# Dev_BRD_STM32F030K6T6.net
KiCad netlist of a schematic drawn in Altium Designer
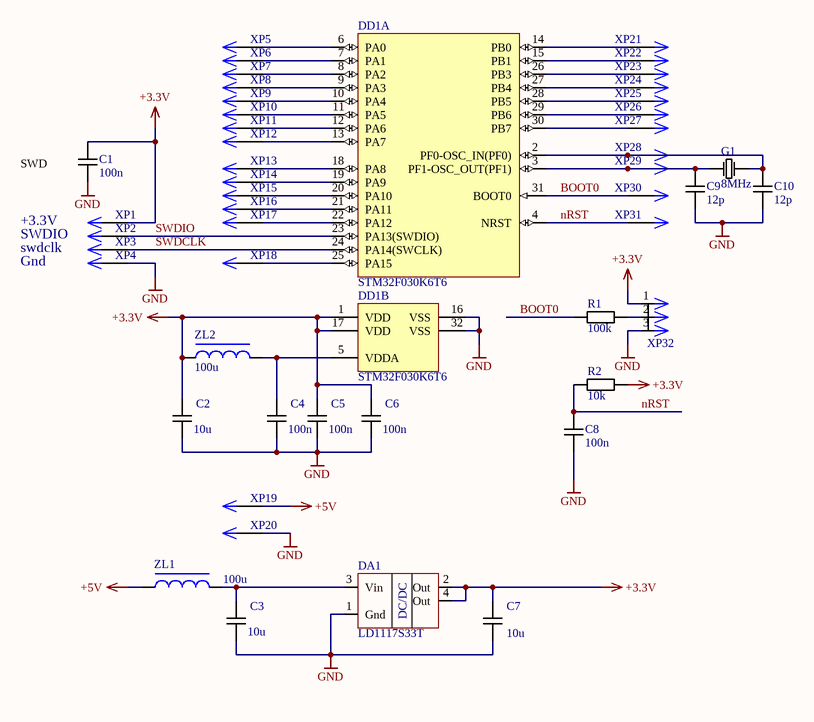
[diagram p0: Dev_BRD_STM32F030K6T6.SchDoc]

(export (version "E")
  (design (tool "Eeschema 10.0.6"))
  (components
    (comp (ref "C1")
      (value "100n")
      (footprint "CAPC1608(0603)N")
      (description "?")
      (fields (field (name "PART NUMBER") "CAPC1608(0603)"))
      (libsource (lib "SssAccesDatbase") (part "Cap"))
    )
    (comp (ref "C2")
      (value "10u")
      (footprint "CAPC1608(0603)N")
      (description "?")
      (fields (field (name "PART NUMBER") "CAPC1608(0603)"))
      (libsource (lib "SssAccesDatbase") (part "Cap"))
    )
    (comp (ref "C3")
      (value "10u")
      (footprint "CAPC1608(0603)N")
      (description "?")
      (fields (field (name "PART NUMBER") "CAPC1608(0603)"))
      (libsource (lib "SssAccesDatbase") (part "Cap"))
    )
    (comp (ref "C4")
      (value "100n")
      (footprint "CAPC1608(0603)N")
      (description "?")
      (fields (field (name "PART NUMBER") "CAPC1608(0603)"))
      (libsource (lib "SssAccesDatbase") (part "Cap"))
    )
    (comp (ref "C5")
      (value "100n")
      (footprint "CAPC1608(0603)N")
      (description "?")
      (fields (field (name "PART NUMBER") "CAPC1608(0603)"))
      (libsource (lib "SssAccesDatbase") (part "Cap"))
    )
    (comp (ref "C6")
      (value "100n")
      (footprint "CAPC1608(0603)N")
      (description "?")
      (fields (field (name "PART NUMBER") "CAPC1608(0603)"))
      (libsource (lib "SssAccesDatbase") (part "Cap"))
    )
    (comp (ref "C7")
      (value "10u")
      (footprint "CAPC1608(0603)N")
      (description "?")
      (fields (field (name "PART NUMBER") "CAPC1608(0603)"))
      (libsource (lib "SssAccesDatbase") (part "Cap"))
    )
    (comp (ref "C8")
      (value "100n")
      (footprint "CAPC1608(0603)N")
      (description "?")
      (fields (field (name "PART NUMBER") "CAPC1608(0603)"))
      (libsource (lib "SssAccesDatbase") (part "Cap"))
    )
    (comp (ref "C9")
      (value "12p")
      (footprint "CAPC1608(0603)N")
      (description "?")
      (fields (field (name "PART NUMBER") "CAPC1608(0603)"))
      (libsource (lib "SssAccesDatbase") (part "Cap"))
    )
    (comp (ref "C10")
      (value "12p")
      (footprint "CAPC1608(0603)N")
      (description "?")
      (fields (field (name "PART NUMBER") "CAPC1608(0603)"))
      (libsource (lib "SssAccesDatbase") (part "Cap"))
    )
    (comp (ref "DA1")
      (value "LD1117S33T")
      (footprint "SOT223_M")
      (description "LDO Voltage Regulators 3.3V 0.8A Positive")
      (fields (field (name "DIGI-KEY PART NUMBER") "?"))
      (libsource (lib "SssAccesDatbase") (part "LD1117S33T"))
    )
    (comp (ref "DD1")
      (value "STM32F030K6T6")
      (footprint "STM-LQFP32_M")
      (description "ARM Microcontrollers - MCU Entry-level ARM Cortex-M0 Value MCU")
      (fields (field (name "MOUSER PART NUMBER") "511-STM32F030K6T6"))
      (libsource (lib "SssAccesDatbase") (part "STM32F030K6T6"))
    )
    (comp (ref "G1")
      (value "8MHz")
      (footprint "HC-49/S")
      (description "Crystal HC-49/S")
      (libsource (lib "SssAccesDatbase") (part "Crystal"))
    )
    (comp (ref "R1")
      (value "100k")
      (footprint "RESC1608(0603)N")
      (fields (field (name "PART NUMBER") "RESC1608(0603)") (field (name "DIGI-KEY PART NUMBER") "???"))
      (libsource (lib "SssAccesDatbase") (part "Resistor general"))
    )
    (comp (ref "R2")
      (value "10k")
      (footprint "RESC1608(0603)N")
      (fields (field (name "PART NUMBER") "RESC1608(0603)") (field (name "DIGI-KEY PART NUMBER") "???"))
      (libsource (lib "") (part "Resistor general_1"))
    )
    (comp (ref "XP1")
      (value "PLS-1")
      (footprint "PLS-1-3D")
      (description "CONN HEADER VERT 1POS")
      (fields
        (field (name "DIGI-KEY PART NUMBER") "S1011EC-01-ND")
        (field (name "MANUFACTURER PART NUMBER") "PRPC001SAAN-RC")
      )
      (libsource (lib "SssAccesDatbase") (part "XP-1_1"))
    )
    (comp (ref "XP2")
      (value "PLS-1")
      (footprint "PLS-1-3D")
      (description "CONN HEADER VERT 1POS")
      (fields
        (field (name "DIGI-KEY PART NUMBER") "S1011EC-01-ND")
        (field (name "MANUFACTURER PART NUMBER") "PRPC001SAAN-RC")
      )
      (libsource (lib "SssAccesDatbase") (part "XP-1_1"))
    )
    (comp (ref "XP3")
      (value "PLS-1")
      (footprint "PLS-1-3D")
      (description "CONN HEADER VERT 1POS")
      (fields
        (field (name "DIGI-KEY PART NUMBER") "S1011EC-01-ND")
        (field (name "MANUFACTURER PART NUMBER") "PRPC001SAAN-RC")
      )
      (libsource (lib "SssAccesDatbase") (part "XP-1_1"))
    )
    (comp (ref "XP4")
      (value "PLS-1")
      (footprint "PLS-1-3D")
      (description "CONN HEADER VERT 1POS")
      (fields
        (field (name "DIGI-KEY PART NUMBER") "S1011EC-01-ND")
        (field (name "MANUFACTURER PART NUMBER") "PRPC001SAAN-RC")
      )
      (libsource (lib "SssAccesDatbase") (part "XP-1_1"))
    )
    (comp (ref "XP5")
      (value "PLS-1")
      (footprint "PLS-1-3D")
      (description "CONN HEADER VERT 1POS")
      (fields
        (field (name "DIGI-KEY PART NUMBER") "S1011EC-01-ND")
        (field (name "MANUFACTURER PART NUMBER") "PRPC001SAAN-RC")
      )
      (libsource (lib "SssAccesDatbase") (part "XP-1_1"))
    )
    (comp (ref "XP6")
      (value "PLS-1")
      (footprint "PLS-1-3D")
      (description "CONN HEADER VERT 1POS")
      (fields
        (field (name "DIGI-KEY PART NUMBER") "S1011EC-01-ND")
        (field (name "MANUFACTURER PART NUMBER") "PRPC001SAAN-RC")
      )
      (libsource (lib "SssAccesDatbase") (part "XP-1_1"))
    )
    (comp (ref "XP7")
      (value "PLS-1")
      (footprint "PLS-1-3D")
      (description "CONN HEADER VERT 1POS")
      (fields
        (field (name "DIGI-KEY PART NUMBER") "S1011EC-01-ND")
        (field (name "MANUFACTURER PART NUMBER") "PRPC001SAAN-RC")
      )
      (libsource (lib "SssAccesDatbase") (part "XP-1_1"))
    )
    (comp (ref "XP8")
      (value "PLS-1")
      (footprint "PLS-1-3D")
      (description "CONN HEADER VERT 1POS")
      (fields
        (field (name "DIGI-KEY PART NUMBER") "S1011EC-01-ND")
        (field (name "MANUFACTURER PART NUMBER") "PRPC001SAAN-RC")
      )
      (libsource (lib "SssAccesDatbase") (part "XP-1_1"))
    )
    (comp (ref "XP9")
      (value "PLS-1")
      (footprint "PLS-1-3D")
      (description "CONN HEADER VERT 1POS")
      (fields
        (field (name "DIGI-KEY PART NUMBER") "S1011EC-01-ND")
        (field (name "MANUFACTURER PART NUMBER") "PRPC001SAAN-RC")
      )
      (libsource (lib "SssAccesDatbase") (part "XP-1_1"))
    )
    (comp (ref "XP10")
      (value "PLS-1")
      (footprint "PLS-1-3D")
      (description "CONN HEADER VERT 1POS")
      (fields
        (field (name "DIGI-KEY PART NUMBER") "S1011EC-01-ND")
        (field (name "MANUFACTURER PART NUMBER") "PRPC001SAAN-RC")
      )
      (libsource (lib "SssAccesDatbase") (part "XP-1_1"))
    )
    (comp (ref "XP11")
      (value "PLS-1")
      (footprint "PLS-1-3D")
      (description "CONN HEADER VERT 1POS")
      (fields
        (field (name "DIGI-KEY PART NUMBER") "S1011EC-01-ND")
        (field (name "MANUFACTURER PART NUMBER") "PRPC001SAAN-RC")
      )
      (libsource (lib "SssAccesDatbase") (part "XP-1_1"))
    )
    (comp (ref "XP12")
      (value "PLS-1")
      (footprint "PLS-1-3D")
      (description "CONN HEADER VERT 1POS")
      (fields
        (field (name "DIGI-KEY PART NUMBER") "S1011EC-01-ND")
        (field (name "MANUFACTURER PART NUMBER") "PRPC001SAAN-RC")
      )
      (libsource (lib "SssAccesDatbase") (part "XP-1_1"))
    )
    (comp (ref "XP13")
      (value "PLS-1")
      (footprint "PLS-1-3D")
      (description "CONN HEADER VERT 1POS")
      (fields
        (field (name "DIGI-KEY PART NUMBER") "S1011EC-01-ND")
        (field (name "MANUFACTURER PART NUMBER") "PRPC001SAAN-RC")
      )
      (libsource (lib "SssAccesDatbase") (part "XP-1_1"))
    )
    (comp (ref "XP14")
      (value "PLS-1")
      (footprint "PLS-1-3D")
      (description "CONN HEADER VERT 1POS")
      (fields
        (field (name "DIGI-KEY PART NUMBER") "S1011EC-01-ND")
        (field (name "MANUFACTURER PART NUMBER") "PRPC001SAAN-RC")
      )
      (libsource (lib "SssAccesDatbase") (part "XP-1_1"))
    )
    (comp (ref "XP15")
      (value "PLS-1")
      (footprint "PLS-1-3D")
      (description "CONN HEADER VERT 1POS")
      (fields
        (field (name "DIGI-KEY PART NUMBER") "S1011EC-01-ND")
        (field (name "MANUFACTURER PART NUMBER") "PRPC001SAAN-RC")
      )
      (libsource (lib "SssAccesDatbase") (part "XP-1_1"))
    )
    (comp (ref "XP16")
      (value "PLS-1")
      (footprint "PLS-1-3D")
      (description "CONN HEADER VERT 1POS")
      (fields
        (field (name "DIGI-KEY PART NUMBER") "S1011EC-01-ND")
        (field (name "MANUFACTURER PART NUMBER") "PRPC001SAAN-RC")
      )
      (libsource (lib "SssAccesDatbase") (part "XP-1_1"))
    )
    (comp (ref "XP17")
      (value "PLS-1")
      (footprint "PLS-1-3D")
      (description "CONN HEADER VERT 1POS")
      (fields
        (field (name "DIGI-KEY PART NUMBER") "S1011EC-01-ND")
        (field (name "MANUFACTURER PART NUMBER") "PRPC001SAAN-RC")
      )
      (libsource (lib "SssAccesDatbase") (part "XP-1_1"))
    )
    (comp (ref "XP18")
      (value "PLS-1")
      (footprint "PLS-1-3D")
      (description "CONN HEADER VERT 1POS")
      (fields
        (field (name "DIGI-KEY PART NUMBER") "S1011EC-01-ND")
        (field (name "MANUFACTURER PART NUMBER") "PRPC001SAAN-RC")
      )
      (libsource (lib "SssAccesDatbase") (part "XP-1_1"))
    )
    (comp (ref "XP19")
      (value "PLS-1")
      (footprint "PLS-1-3D")
      (description "CONN HEADER VERT 1POS")
      (fields
        (field (name "DIGI-KEY PART NUMBER") "S1011EC-01-ND")
        (field (name "MANUFACTURER PART NUMBER") "PRPC001SAAN-RC")
      )
      (libsource (lib "SssAccesDatbase") (part "XP-1_1"))
    )
    (comp (ref "XP20")
      (value "PLS-1")
      (footprint "PLS-1-3D")
      (description "CONN HEADER VERT 1POS")
      (fields
        (field (name "DIGI-KEY PART NUMBER") "S1011EC-01-ND")
        (field (name "MANUFACTURER PART NUMBER") "PRPC001SAAN-RC")
      )
      (libsource (lib "SssAccesDatbase") (part "XP-1_1"))
    )
    (comp (ref "XP21")
      (value "PLS-1")
      (footprint "PLS-1-3D")
      (description "CONN HEADER VERT 1POS")
      (fields
        (field (name "DIGI-KEY PART NUMBER") "S1011EC-01-ND")
        (field (name "MANUFACTURER PART NUMBER") "PRPC001SAAN-RC")
      )
      (libsource (lib "SssAccesDatbase") (part "XP-1_1"))
    )
    (comp (ref "XP22")
      (value "PLS-1")
      (footprint "PLS-1-3D")
      (description "CONN HEADER VERT 1POS")
      (fields
        (field (name "DIGI-KEY PART NUMBER") "S1011EC-01-ND")
        (field (name "MANUFACTURER PART NUMBER") "PRPC001SAAN-RC")
      )
      (libsource (lib "SssAccesDatbase") (part "XP-1_1"))
    )
    (comp (ref "XP23")
      (value "PLS-1")
      (footprint "PLS-1-3D")
      (description "CONN HEADER VERT 1POS")
      (fields
        (field (name "DIGI-KEY PART NUMBER") "S1011EC-01-ND")
        (field (name "MANUFACTURER PART NUMBER") "PRPC001SAAN-RC")
      )
      (libsource (lib "SssAccesDatbase") (part "XP-1_1"))
    )
    (comp (ref "XP24")
      (value "PLS-1")
      (footprint "PLS-1-3D")
      (description "CONN HEADER VERT 1POS")
      (fields
        (field (name "DIGI-KEY PART NUMBER") "S1011EC-01-ND")
        (field (name "MANUFACTURER PART NUMBER") "PRPC001SAAN-RC")
      )
      (libsource (lib "SssAccesDatbase") (part "XP-1_1"))
    )
    (comp (ref "XP25")
      (value "PLS-1")
      (footprint "PLS-1-3D")
      (description "CONN HEADER VERT 1POS")
      (fields
        (field (name "DIGI-KEY PART NUMBER") "S1011EC-01-ND")
        (field (name "MANUFACTURER PART NUMBER") "PRPC001SAAN-RC")
      )
      (libsource (lib "SssAccesDatbase") (part "XP-1_1"))
    )
    (comp (ref "XP26")
      (value "PLS-1")
      (footprint "PLS-1-3D")
      (description "CONN HEADER VERT 1POS")
      (fields
        (field (name "DIGI-KEY PART NUMBER") "S1011EC-01-ND")
        (field (name "MANUFACTURER PART NUMBER") "PRPC001SAAN-RC")
      )
      (libsource (lib "SssAccesDatbase") (part "XP-1_1"))
    )
    (comp (ref "XP27")
      (value "PLS-1")
      (footprint "PLS-1-3D")
      (description "CONN HEADER VERT 1POS")
      (fields
        (field (name "DIGI-KEY PART NUMBER") "S1011EC-01-ND")
        (field (name "MANUFACTURER PART NUMBER") "PRPC001SAAN-RC")
      )
      (libsource (lib "SssAccesDatbase") (part "XP-1_1"))
    )
    (comp (ref "XP28")
      (value "PLS-1")
      (footprint "PLS-1-3D")
      (description "CONN HEADER VERT 1POS")
      (fields
        (field (name "DIGI-KEY PART NUMBER") "S1011EC-01-ND")
        (field (name "MANUFACTURER PART NUMBER") "PRPC001SAAN-RC")
      )
      (libsource (lib "SssAccesDatbase") (part "XP-1_1"))
    )
    (comp (ref "XP29")
      (value "PLS-1")
      (footprint "PLS-1-3D")
      (description "CONN HEADER VERT 1POS")
      (fields
        (field (name "DIGI-KEY PART NUMBER") "S1011EC-01-ND")
        (field (name "MANUFACTURER PART NUMBER") "PRPC001SAAN-RC")
      )
      (libsource (lib "SssAccesDatbase") (part "XP-1_1"))
    )
    (comp (ref "XP30")
      (value "PLS-1")
      (footprint "PLS-1-3D")
      (description "CONN HEADER VERT 1POS")
      (fields
        (field (name "DIGI-KEY PART NUMBER") "S1011EC-01-ND")
        (field (name "MANUFACTURER PART NUMBER") "PRPC001SAAN-RC")
      )
      (libsource (lib "SssAccesDatbase") (part "XP-1_1"))
    )
    (comp (ref "XP31")
      (value "PLS-1")
      (footprint "PLS-1-3D")
      (description "CONN HEADER VERT 1POS")
      (fields
        (field (name "DIGI-KEY PART NUMBER") "S1011EC-01-ND")
        (field (name "MANUFACTURER PART NUMBER") "PRPC001SAAN-RC")
      )
      (libsource (lib "SssAccesDatbase") (part "XP-1_1"))
    )
    (comp (ref "XP32")
      (value "PLS-3")
      (footprint "PLS-3-3D")
      (description "CONN HEADER VERT 3POS 2.54MM")
      (fields (field (name "PART NUMBER") "PR20203VBNN") (field (name "DIGI-KEY PART NUMBER") "1849-1003-ND"))
      (libsource (lib "SssAccesDatbase") (part "XP-3_Jump"))
    )
    (comp (ref "ZL1")
      (value "100u")
      (footprint "INDC1608(0603)N")
      (description "ferite bead")
      (fields (field (name "PART NUMBER") "Ferite1608(0603)") (field (name "DIGI-KEY PART NUMBER") "???"))
      (libsource (lib "SssAccesDatbase") (part "ZL"))
    )
    (comp (ref "ZL2")
      (value "100u")
      (footprint "INDC1608(0603)N")
      (description "ferite bead")
      (fields (field (name "PART NUMBER") "Ferite1608(0603)") (field (name "DIGI-KEY PART NUMBER") "???"))
      (libsource (lib "SssAccesDatbase") (part "ZL"))
    )
  )
  (nets
    (net (code "1") (name "+3.3V") (class "Default")
      (node (ref "C1") (pin "1") (pinfunction "1_1") (pintype "passive"))
      (node (ref "C2") (pin "2") (pinfunction "2_2") (pintype "passive"))
      (node (ref "C5") (pin "2") (pinfunction "2_2") (pintype "passive"))
      (node (ref "C6") (pin "2") (pinfunction "2_2") (pintype "passive"))
      (node (ref "C7") (pin "2") (pinfunction "2_2") (pintype "passive"))
      (node (ref "DA1") (pin "2") (pinfunction "Out_2") (pintype "passive"))
      (node (ref "DA1") (pin "4") (pinfunction "Out_4") (pintype "passive"))
      (node (ref "DD1") (pin "1") (pinfunction "VDD_1") (pintype "power_in"))
      (node (ref "DD1") (pin "17") (pinfunction "VDD_17") (pintype "power_in"))
      (node (ref "R2") (pin "2") (pinfunction "2_2") (pintype "passive"))
      (node (ref "XP1") (pin "1") (pinfunction "1_1") (pintype "passive"))
      (node (ref "XP32") (pin "1") (pinfunction "1_1") (pintype "passive"))
      (node (ref "ZL2") (pin "1") (pinfunction "1_1") (pintype "passive"))
    )
    (net (code "2") (name "+5V") (class "Default")
      (node (ref "XP19") (pin "1") (pinfunction "1_1") (pintype "passive"))
      (node (ref "ZL1") (pin "1") (pinfunction "1_1") (pintype "passive"))
    )
    (net (code "3") (name "/BOOT0") (class "Default")
      (node (ref "DD1") (pin "31") (pinfunction "BOOT0_31") (pintype "input"))
      (node (ref "R1") (pin "1") (pinfunction "1_1") (pintype "passive"))
      (node (ref "XP30") (pin "1") (pinfunction "1_1") (pintype "passive"))
    )
    (net (code "4") (name "/SWDCLK") (class "Default")
      (node (ref "DD1") (pin "24") (pinfunction "PA14(SWCLK)_24") (pintype "bidirectional"))
      (node (ref "XP3") (pin "1") (pinfunction "1_1") (pintype "passive"))
    )
    (net (code "5") (name "/SWDIO") (class "Default")
      (node (ref "DD1") (pin "23") (pinfunction "PA13(SWDIO)_23") (pintype "bidirectional"))
      (node (ref "XP2") (pin "1") (pinfunction "1_1") (pintype "passive"))
    )
    (net (code "6") (name "/nRST") (class "Default")
      (node (ref "C8") (pin "2") (pinfunction "2_2") (pintype "passive"))
      (node (ref "DD1") (pin "4") (pinfunction "NRST_4") (pintype "bidirectional"))
      (node (ref "R2") (pin "1") (pinfunction "1_1") (pintype "passive"))
      (node (ref "XP31") (pin "1") (pinfunction "1_1") (pintype "passive"))
    )
    (net (code "7") (name "GND") (class "Default")
      (node (ref "C1") (pin "2") (pinfunction "2_2") (pintype "passive"))
      (node (ref "C10") (pin "1") (pinfunction "1_1") (pintype "passive"))
      (node (ref "C2") (pin "1") (pinfunction "1_1") (pintype "passive"))
      (node (ref "C3") (pin "1") (pinfunction "1_1") (pintype "passive"))
      (node (ref "C4") (pin "1") (pinfunction "1_1") (pintype "passive"))
      (node (ref "C5") (pin "1") (pinfunction "1_1") (pintype "passive"))
      (node (ref "C6") (pin "1") (pinfunction "1_1") (pintype "passive"))
      (node (ref "C7") (pin "1") (pinfunction "1_1") (pintype "passive"))
      (node (ref "C8") (pin "1") (pinfunction "1_1") (pintype "passive"))
      (node (ref "C9") (pin "1") (pinfunction "1_1") (pintype "passive"))
      (node (ref "DA1") (pin "1") (pinfunction "Gnd_1") (pintype "passive"))
      (node (ref "DD1") (pin "16") (pinfunction "VSS_16") (pintype "power_in"))
      (node (ref "DD1") (pin "32") (pinfunction "VSS_32") (pintype "power_in"))
      (node (ref "XP20") (pin "1") (pinfunction "1_1") (pintype "passive"))
      (node (ref "XP32") (pin "3") (pinfunction "3_3") (pintype "passive"))
      (node (ref "XP4") (pin "1") (pinfunction "1_1") (pintype "passive"))
    )
    (net (code "8") (name "Net-(DA1-Vin)") (class "Default")
      (node (ref "C3") (pin "2") (pinfunction "2_2") (pintype "passive"))
      (node (ref "DA1") (pin "3") (pinfunction "Vin_3") (pintype "passive"))
      (node (ref "ZL1") (pin "2") (pinfunction "2_2") (pintype "passive"))
    )
    (net (code "9") (name "Net-(DD1A-PA0)") (class "Default")
      (node (ref "DD1") (pin "6") (pinfunction "PA0_6") (pintype "bidirectional"))
      (node (ref "XP5") (pin "1") (pinfunction "1_1") (pintype "passive"))
    )
    (net (code "10") (name "Net-(DD1A-PA1)") (class "Default")
      (node (ref "DD1") (pin "7") (pinfunction "PA1_7") (pintype "bidirectional"))
      (node (ref "XP6") (pin "1") (pinfunction "1_1") (pintype "passive"))
    )
    (net (code "11") (name "Net-(DD1A-PA2)") (class "Default")
      (node (ref "DD1") (pin "8") (pinfunction "PA2_8") (pintype "bidirectional"))
      (node (ref "XP7") (pin "1") (pinfunction "1_1") (pintype "passive"))
    )
    (net (code "12") (name "Net-(DD1A-PA3)") (class "Default")
      (node (ref "DD1") (pin "9") (pinfunction "PA3_9") (pintype "bidirectional"))
      (node (ref "XP8") (pin "1") (pinfunction "1_1") (pintype "passive"))
    )
    (net (code "13") (name "Net-(DD1A-PA4)") (class "Default")
      (node (ref "DD1") (pin "10") (pinfunction "PA4_10") (pintype "bidirectional"))
      (node (ref "XP9") (pin "1") (pinfunction "1_1") (pintype "passive"))
    )
    (net (code "14") (name "Net-(DD1A-PA5)") (class "Default")
      (node (ref "DD1") (pin "11") (pinfunction "PA5_11") (pintype "bidirectional"))
      (node (ref "XP10") (pin "1") (pinfunction "1_1") (pintype "passive"))
    )
    (net (code "15") (name "Net-(DD1A-PA6)") (class "Default")
      (node (ref "DD1") (pin "12") (pinfunction "PA6_12") (pintype "bidirectional"))
      (node (ref "XP11") (pin "1") (pinfunction "1_1") (pintype "passive"))
    )
    (net (code "16") (name "Net-(DD1A-PA7)") (class "Default")
      (node (ref "DD1") (pin "13") (pinfunction "PA7_13") (pintype "bidirectional"))
      (node (ref "XP12") (pin "1") (pinfunction "1_1") (pintype "passive"))
    )
    (net (code "17") (name "Net-(DD1A-PA8)") (class "Default")
      (node (ref "DD1") (pin "18") (pinfunction "PA8_18") (pintype "bidirectional"))
      (node (ref "XP13") (pin "1") (pinfunction "1_1") (pintype "passive"))
    )
    (net (code "18") (name "Net-(DD1A-PA9)") (class "Default")
      (node (ref "DD1") (pin "19") (pinfunction "PA9_19") (pintype "bidirectional"))
      (node (ref "XP14") (pin "1") (pinfunction "1_1") (pintype "passive"))
    )
    (net (code "19") (name "Net-(DD1A-PA10)") (class "Default")
      (node (ref "DD1") (pin "20") (pinfunction "PA10_20") (pintype "bidirectional"))
      (node (ref "XP15") (pin "1") (pinfunction "1_1") (pintype "passive"))
    )
    (net (code "20") (name "Net-(DD1A-PA11)") (class "Default")
      (node (ref "DD1") (pin "21") (pinfunction "PA11_21") (pintype "bidirectional"))
      (node (ref "XP16") (pin "1") (pinfunction "1_1") (pintype "passive"))
    )
    (net (code "21") (name "Net-(DD1A-PA12)") (class "Default")
      (node (ref "DD1") (pin "22") (pinfunction "PA12_22") (pintype "bidirectional"))
      (node (ref "XP17") (pin "1") (pinfunction "1_1") (pintype "passive"))
    )
    (net (code "22") (name "Net-(DD1A-PA15)") (class "Default")
      (node (ref "DD1") (pin "25") (pinfunction "PA15_25") (pintype "bidirectional"))
      (node (ref "XP18") (pin "1") (pinfunction "1_1") (pintype "passive"))
    )
    (net (code "23") (name "Net-(DD1A-PB0)") (class "Default")
      (node (ref "DD1") (pin "14") (pinfunction "PB0_14") (pintype "bidirectional"))
      (node (ref "XP21") (pin "1") (pinfunction "1_1") (pintype "passive"))
    )
    (net (code "24") (name "Net-(DD1A-PB1)") (class "Default")
      (node (ref "DD1") (pin "15") (pinfunction "PB1_15") (pintype "bidirectional"))
      (node (ref "XP22") (pin "1") (pinfunction "1_1") (pintype "passive"))
    )
    (net (code "25") (name "Net-(DD1A-PB3)") (class "Default")
      (node (ref "DD1") (pin "26") (pinfunction "PB3_26") (pintype "bidirectional"))
      (node (ref "XP23") (pin "1") (pinfunction "1_1") (pintype "passive"))
    )
    (net (code "26") (name "Net-(DD1A-PB4)") (class "Default")
      (node (ref "DD1") (pin "27") (pinfunction "PB4_27") (pintype "bidirectional"))
      (node (ref "XP24") (pin "1") (pinfunction "1_1") (pintype "passive"))
    )
    (net (code "27") (name "Net-(DD1A-PB5)") (class "Default")
      (node (ref "DD1") (pin "28") (pinfunction "PB5_28") (pintype "bidirectional"))
      (node (ref "XP25") (pin "1") (pinfunction "1_1") (pintype "passive"))
    )
    (net (code "28") (name "Net-(DD1A-PB6)") (class "Default")
      (node (ref "DD1") (pin "29") (pinfunction "PB6_29") (pintype "bidirectional"))
      (node (ref "XP26") (pin "1") (pinfunction "1_1") (pintype "passive"))
    )
    (net (code "29") (name "Net-(DD1A-PB7)") (class "Default")
      (node (ref "DD1") (pin "30") (pinfunction "PB7_30") (pintype "bidirectional"))
      (node (ref "XP27") (pin "1") (pinfunction "1_1") (pintype "passive"))
    )
    (net (code "30") (name "Net-(DD1A-PF0-OSC_IN(PF0))") (class "Default")
      (node (ref "C10") (pin "2") (pinfunction "2_2") (pintype "passive"))
      (node (ref "DD1") (pin "2") (pinfunction "PF0-OSC_IN(PF0)_2") (pintype "bidirectional"))
      (node (ref "G1") (pin "2") (pinfunction "2_2") (pintype "passive"))
      (node (ref "XP28") (pin "1") (pinfunction "1_1") (pintype "passive"))
    )
    (net (code "31") (name "Net-(DD1A-PF1-OSC_OUT(PF1))") (class "Default")
      (node (ref "C9") (pin "2") (pinfunction "2_2") (pintype "passive"))
      (node (ref "DD1") (pin "3") (pinfunction "PF1-OSC_OUT(PF1)_3") (pintype "bidirectional"))
      (node (ref "G1") (pin "1") (pinfunction "1_1") (pintype "passive"))
      (node (ref "XP29") (pin "1") (pinfunction "1_1") (pintype "passive"))
    )
    (net (code "32") (name "Net-(DD1B-VDDA)") (class "Default")
      (node (ref "C4") (pin "2") (pinfunction "2_2") (pintype "passive"))
      (node (ref "DD1") (pin "5") (pinfunction "VDDA_5") (pintype "power_in"))
      (node (ref "ZL2") (pin "2") (pinfunction "2_2") (pintype "passive"))
    )
    (net (code "33") (name "Net-(R1-Pad2)") (class "Default")
      (node (ref "R1") (pin "2") (pinfunction "2_2") (pintype "passive"))
      (node (ref "XP32") (pin "2") (pinfunction "2_2") (pintype "passive"))
    )
  )
)
